# T962a-P1.net
KiCad netlist of a schematic drawn in Altium Designer
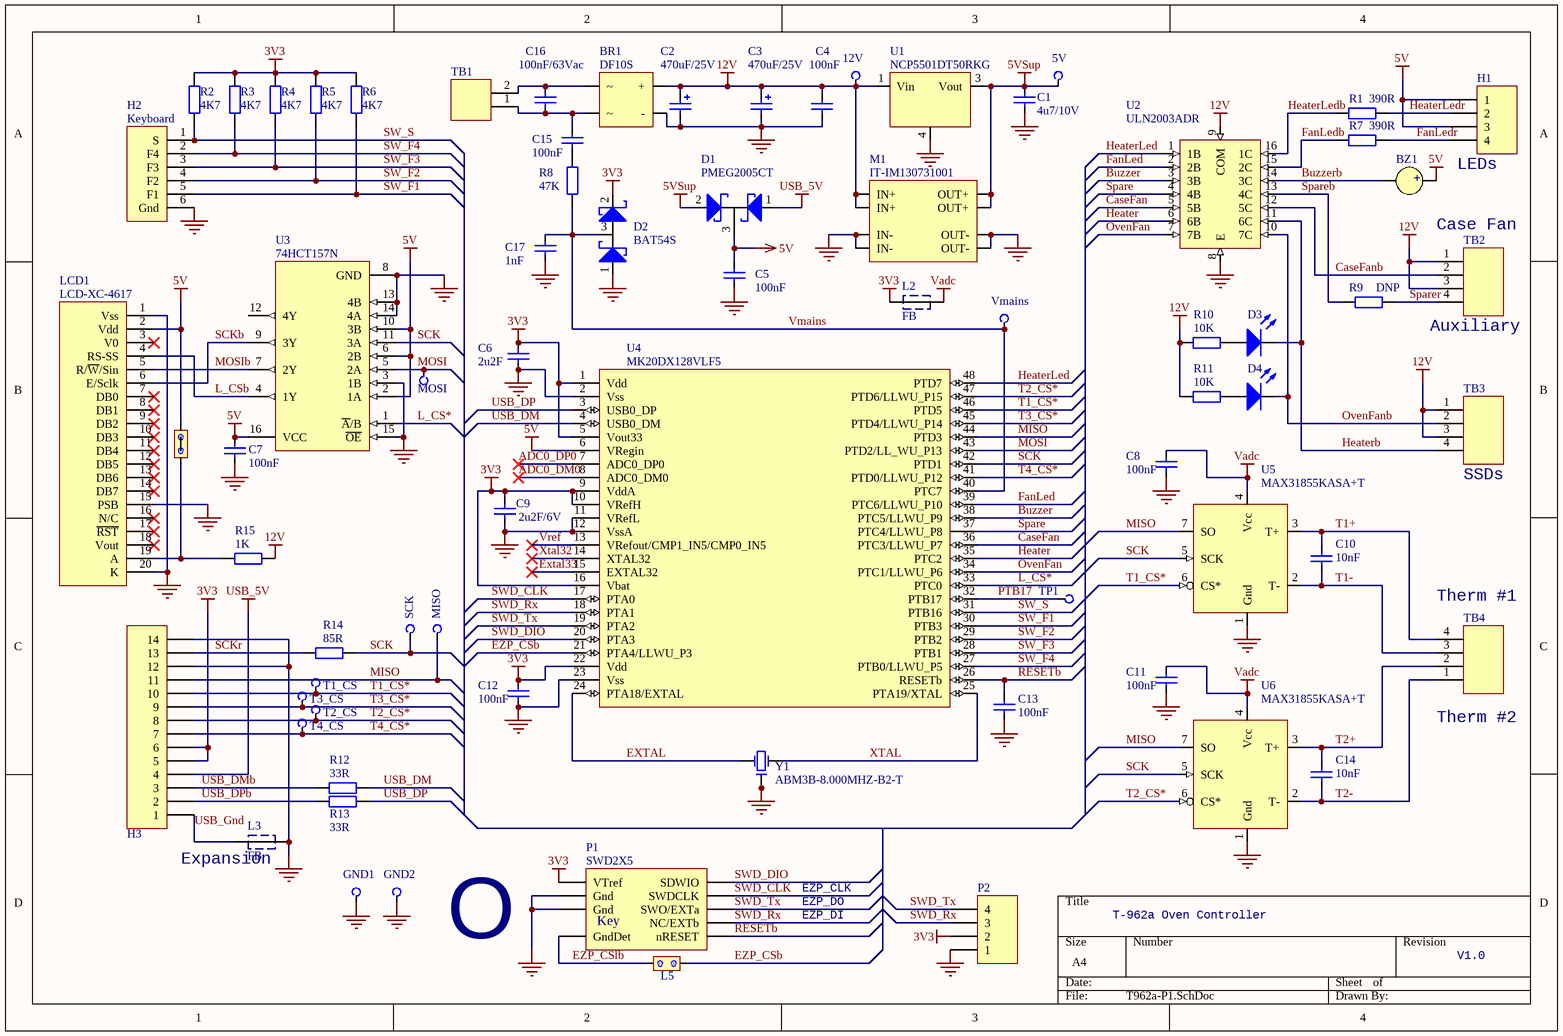
[diagram p0: T962a-P1.SchDoc]

(export (version "E")
  (design (tool "Eeschema 10.0.6"))
  (components
    (comp (ref "5V")
      (value "TP")
      (footprint "PCBPIN - 0.9mm")
      (description "Test Point")
      (libsource (lib "MyLibrary") (part "TP"))
    )
    (comp (ref "12V")
      (value "TP")
      (footprint "PCBPIN - 0.9mm")
      (description "Test Point")
      (libsource (lib "MyLibrary") (part "TP"))
    )
    (comp (ref "BR1")
      (value "DF10S")
      (footprint "Bridge-SMT")
      (description "bRIDGE rECTIFIER")
      (libsource (lib "MySchLib") (part "DF10S"))
    )
    (comp (ref "BZ1")
      (value "Buzzer_PCB")
      (footprint "BUZZER_Small")
      (description "Buzzer (Adafruit 1536)")
      (libsource (lib "MyLibrary") (part "Buzzer_PCB"))
    )
    (comp (ref "C1")
      (value "4u7/10V")
      (footprint "CCNP2012-0805")
      (description "Capacitor SMT 0805")
      (fields
        (field (name "MANUFACTURER") "Generic Components")
        (field (name "PUBLISHER") "Altium Hobart Technology Centre")
      )
      (libsource (lib "MyLibrary") (part "Cap_CCNP_0805"))
    )
    (comp (ref "C2")
      (value "470uF/25V")
      (footprint "RB5/10x13mm")
      (description "Polarized Capacitor")
      (fields
        (field (name "MANUFACTURER") "Generic Components")
        (field (name "PUBLISHER") "Altium Hobart Technology Centre")
      )
      (libsource (lib "MySchLib") (part "Cap-25ZLS470MEFC10X12"))
    )
    (comp (ref "C3")
      (value "470uF/25V")
      (footprint "RB5/10x13mm")
      (description "Polarized Capacitor")
      (fields
        (field (name "MANUFACTURER") "Generic Components")
        (field (name "PUBLISHER") "Altium Hobart Technology Centre")
      )
      (libsource (lib "MySchLib") (part "Cap-25ZLS470MEFC10X12"))
    )
    (comp (ref "C4")
      (value "100nF")
      (footprint "CCNP2012-0805")
      (description "Capacitor")
      (fields
        (field (name "MANUFACTURER") "Generic Components")
        (field (name "PUBLISHER") "Altium Hobart Technology Centre")
      )
      (libsource (lib "MyLibrary") (part "Cap"))
    )
    (comp (ref "C5")
      (value "100nF")
      (footprint "CCNP2012-0805")
      (description "Capacitor")
      (fields
        (field (name "MANUFACTURER") "Generic Components")
        (field (name "PUBLISHER") "Altium Hobart Technology Centre")
      )
      (libsource (lib "MyLibrary") (part "Cap"))
    )
    (comp (ref "C6")
      (value "2u2F")
      (footprint "CCNP2012-0805")
      (description "Capacitor")
      (fields
        (field (name "MANUFACTURER") "Generic Components")
        (field (name "PUBLISHER") "Altium Hobart Technology Centre")
      )
      (libsource (lib "MyLibrary") (part "Cap"))
    )
    (comp (ref "C7")
      (value "100nF")
      (footprint "CCNP2012-0805")
      (description "Capacitor")
      (fields
        (field (name "MANUFACTURER") "Generic Components")
        (field (name "PUBLISHER") "Altium Hobart Technology Centre")
      )
      (libsource (lib "MyLibrary") (part "Cap"))
    )
    (comp (ref "C8")
      (value "100nF")
      (footprint "CCNP2012-0805")
      (description "Capacitor SMT 0805")
      (fields
        (field (name "MANUFACTURER") "Generic Components")
        (field (name "PUBLISHER") "Altium Hobart Technology Centre")
      )
      (libsource (lib "MyLibrary") (part "Cap_CCNP_0805"))
    )
    (comp (ref "C9")
      (value "2u2F/6V")
      (footprint "CCNP2012-0805")
      (description "Capacitor")
      (fields
        (field (name "MANUFACTURER") "Generic Components")
        (field (name "PUBLISHER") "Altium Hobart Technology Centre")
      )
      (libsource (lib "MyLibrary") (part "Cap"))
    )
    (comp (ref "C10")
      (value "10nF")
      (footprint "CCNP2012-0805")
      (description "Capacitor SMT 0805")
      (fields
        (field (name "MANUFACTURER") "Generic Components")
        (field (name "PUBLISHER") "Altium Hobart Technology Centre")
      )
      (libsource (lib "MyLibrary") (part "Cap_CCNP_0805"))
    )
    (comp (ref "C11")
      (value "100nF")
      (footprint "CCNP2012-0805")
      (description "Capacitor SMT 0805")
      (fields
        (field (name "MANUFACTURER") "Generic Components")
        (field (name "PUBLISHER") "Altium Hobart Technology Centre")
      )
      (libsource (lib "MyLibrary") (part "Cap_CCNP_0805"))
    )
    (comp (ref "C12")
      (value "100nF")
      (footprint "CCNP2012-0805")
      (description "Capacitor")
      (fields
        (field (name "MANUFACTURER") "Generic Components")
        (field (name "PUBLISHER") "Altium Hobart Technology Centre")
      )
      (libsource (lib "MyLibrary") (part "Cap"))
    )
    (comp (ref "C13")
      (value "100nF")
      (footprint "CCNP2012-0805")
      (description "Capacitor SMT 0805")
      (fields
        (field (name "MANUFACTURER") "Generic Components")
        (field (name "PUBLISHER") "Altium Hobart Technology Centre")
      )
      (libsource (lib "MyLibrary") (part "Cap_CCNP_0805"))
    )
    (comp (ref "C14")
      (value "10nF")
      (footprint "CCNP2012-0805")
      (description "Capacitor SMT 0805")
      (fields
        (field (name "MANUFACTURER") "Generic Components")
        (field (name "PUBLISHER") "Altium Hobart Technology Centre")
      )
      (libsource (lib "MyLibrary") (part "Cap_CCNP_0805"))
    )
    (comp (ref "C15")
      (value "100nF")
      (footprint "CCNP2012-0805")
      (description "Capacitor")
      (fields
        (field (name "MANUFACTURER") "Generic Components")
        (field (name "PUBLISHER") "Altium Hobart Technology Centre")
      )
      (libsource (lib "MyLibrary") (part "Cap"))
    )
    (comp (ref "C16")
      (value "100nF/63Vac")
      (footprint "CAP - small MKT")
      (description "Capacitor")
      (fields
        (field (name "MANUFACTURER") "Generic Components")
        (field (name "PUBLISHER") "Altium Hobart Technology Centre")
      )
      (libsource (lib "MyLibrary") (part "Cap"))
    )
    (comp (ref "C17")
      (value "1nF")
      (footprint "CCNP2012-0805")
      (description "Capacitor")
      (fields
        (field (name "MANUFACTURER") "Generic Components")
        (field (name "PUBLISHER") "Altium Hobart Technology Centre")
      )
      (libsource (lib "MyLibrary") (part "Cap"))
    )
    (comp (ref "D1")
      (value "PMEG2005CT")
      (footprint "SOT23")
      (description "Dual Schottky Diode (SMT)")
      (libsource (lib "MyLibrary") (part "PMEG2005CT"))
    )
    (comp (ref "D2")
      (value "BAT54S")
      (footprint "SOT23")
      (description "Dual Diode (SMT)")
      (libsource (lib "MyLibrary") (part "BAT54S"))
    )
    (comp (ref "D3")
      (value "LED Red")
      (footprint "LED-SMT-2")
      (description "LED (Red SMT)")
      (fields (field (name "MANUFACTURER") "Generic Components") (field (name "PUBLISHER") "Altium Limited"))
      (libsource (lib "MyLibrary") (part "LED SMT,Red"))
    )
    (comp (ref "D4")
      (value "LED Red")
      (footprint "LED-SMT-2")
      (description "LED (Red SMT)")
      (fields (field (name "MANUFACTURER") "Generic Components") (field (name "PUBLISHER") "Altium Limited"))
      (libsource (lib "MyLibrary") (part "LED SMT,Red"))
    )
    (comp (ref "GND1")
      (value "TP")
      (footprint "PCBPIN - 0.9mm")
      (description "Test Point")
      (libsource (lib "MyLibrary") (part "TP"))
    )
    (comp (ref "GND2")
      (value "TP")
      (footprint "PCBPIN - 0.9mm")
      (description "Test Point")
      (libsource (lib "MyLibrary") (part "TP"))
    )
    (comp (ref "H1")
      (value "Header 1x4")
      (footprint "HDR1X4S")
      (description "Header, 5-Pin, Right Angle")
      (fields (field (name "PUBLISHER") "Altium Limited"))
      (libsource (lib "") (part "Header 1x4_1"))
    )
    (comp (ref "H2")
      (value "Keyboard")
      (footprint "HDR1X6H")
      (description "Header, 6-Pin")
      (fields (field (name "PUBLISHER") "Altium Limited"))
      (libsource (lib "Miscellaneous Connectors") (part "Header 6"))
    )
    (comp (ref "H3")
      (value "2x5 Header")
      (footprint "HDR2X7H")
      (description "Header 2x7")
      (libsource (lib "MyLibrary") (part "Header 2x7H"))
    )
    (comp (ref "L2")
      (value "FB")
      (footprint "CR2012-0805")
      (description "Ferrite Bead (0805) 0.045OHM, 2A")
      (libsource (lib "MyLibrary") (part "Ferrite Bead 0805"))
    )
    (comp (ref "L3")
      (value "FB")
      (footprint "CR2012-0805")
      (description "Ferrite Bead (0805) 0.045OHM, 2A")
      (libsource (lib "MyLibrary") (part "Ferrite Bead 0805"))
    )
    (comp (ref "L5")
      (value "LinkOpen")
      (footprint "SolderBridge(Open)")
      (libsource (lib "MyLibrary") (part "LinkOpen"))
    )
    (comp (ref "L6")
      (value "LinkClosed")
      (footprint "SolderBridge(Closed)")
      (libsource (lib "MyLibrary") (part "LinkClosed"))
    )
    (comp (ref "LCD1")
      (value "LCD-XC-4617")
      (footprint "LCD_XC-4617")
      (description "LCD 128 x 64 pixel, ST7920 controller & contrast pot (Jaycar XC-4617)")
      (libsource (lib "MyLibrary") (part "LCD-XC-4617"))
    )
    (comp (ref "Logo1")
      (value "OSHW Logo")
      (footprint "OSHW")
      (libsource (lib "MyLibrary") (part "OSHW Logo"))
    )
    (comp (ref "M1")
      (value "IT-IM130731001")
      (footprint "IT-IM130731001")
      (description "Itead Buck converter")
      (libsource (lib "MyLibrary") (part "IT-IM130731001"))
    )
    (comp (ref "MISO")
      (value "TP")
      (footprint "PCBPIN - 0.9mm")
      (description "Test Point")
      (libsource (lib "MyLibrary") (part "TP"))
    )
    (comp (ref "MOSI")
      (value "TP")
      (footprint "PCBPIN - 0.9mm")
      (description "Test Point")
      (libsource (lib "MyLibrary") (part "TP"))
    )
    (comp (ref "P1")
      (value "SWD2X5")
      (footprint "SWD-2x5")
      (description "SWD Connector 2x5-Pin")
      (fields (field (name "PUBLISHER") "Altium Limited"))
      (libsource (lib "MySchLib") (part "SWD2X5"))
    )
    (comp (ref "P2")
      (value "Header 1x4")
      (footprint "HDR1X4S")
      (description "Header, 5-Pin, Right Angle")
      (fields (field (name "PUBLISHER") "Altium Limited"))
      (libsource (lib "MyLibrary") (part "Header 1x4"))
    )
    (comp (ref "R1")
      (value "390R")
      (footprint "CR2012-0805")
      (description "Resistor")
      (fields
        (field (name "MANUFACTURER") "Generic Components")
        (field (name "PUBLISHER") "Altium Hobart Technology Centre")
      )
      (libsource (lib "") (part "Res_CR0805_1"))
    )
    (comp (ref "R2")
      (value "4K7")
      (footprint "CR2012-0805")
      (description "Resistor")
      (fields
        (field (name "MANUFACTURER") "Generic Components")
        (field (name "PUBLISHER") "Altium Hobart Technology Centre")
      )
      (libsource (lib "MyLibrary") (part "Res_CR0805"))
    )
    (comp (ref "R3")
      (value "4K7")
      (footprint "CR2012-0805")
      (description "Resistor")
      (fields
        (field (name "MANUFACTURER") "Generic Components")
        (field (name "PUBLISHER") "Altium Hobart Technology Centre")
      )
      (libsource (lib "MyLibrary") (part "Res_CR0805"))
    )
    (comp (ref "R4")
      (value "4K7")
      (footprint "CR2012-0805")
      (description "Resistor")
      (fields
        (field (name "MANUFACTURER") "Generic Components")
        (field (name "PUBLISHER") "Altium Hobart Technology Centre")
      )
      (libsource (lib "MyLibrary") (part "Res_CR0805"))
    )
    (comp (ref "R5")
      (value "4K7")
      (footprint "CR2012-0805")
      (description "Resistor")
      (fields
        (field (name "MANUFACTURER") "Generic Components")
        (field (name "PUBLISHER") "Altium Hobart Technology Centre")
      )
      (libsource (lib "MyLibrary") (part "Res_CR0805"))
    )
    (comp (ref "R6")
      (value "4K7")
      (footprint "CR2012-0805")
      (description "Resistor")
      (fields
        (field (name "MANUFACTURER") "Generic Components")
        (field (name "PUBLISHER") "Altium Hobart Technology Centre")
      )
      (libsource (lib "MyLibrary") (part "Res_CR0805"))
    )
    (comp (ref "R7")
      (value "390R")
      (footprint "CR2012-0805")
      (description "Resistor")
      (fields
        (field (name "MANUFACTURER") "Generic Components")
        (field (name "PUBLISHER") "Altium Hobart Technology Centre")
      )
      (libsource (lib "") (part "Res_CR0805_1"))
    )
    (comp (ref "R8")
      (value "47K")
      (footprint "CR2012-0805")
      (description "Resistor")
      (fields
        (field (name "MANUFACTURER") "Generic Components")
        (field (name "PUBLISHER") "Altium Hobart Technology Centre")
      )
      (libsource (lib "MyLibrary") (part "Res_CR0805"))
    )
    (comp (ref "R9")
      (value "DNP")
      (footprint "CR2012-0805")
      (description "Resistor")
      (fields
        (field (name "MANUFACTURER") "Generic Components")
        (field (name "PUBLISHER") "Altium Hobart Technology Centre")
      )
      (libsource (lib "") (part "Res_CR0805_1"))
    )
    (comp (ref "R10")
      (value "10K")
      (footprint "CR2012-0805")
      (description "Resistor")
      (fields
        (field (name "MANUFACTURER") "Generic Components")
        (field (name "PUBLISHER") "Altium Hobart Technology Centre")
      )
      (libsource (lib "") (part "Res_CR0805_1"))
    )
    (comp (ref "R11")
      (value "10K")
      (footprint "CR2012-0805")
      (description "Resistor")
      (fields
        (field (name "MANUFACTURER") "Generic Components")
        (field (name "PUBLISHER") "Altium Hobart Technology Centre")
      )
      (libsource (lib "") (part "Res_CR0805_1"))
    )
    (comp (ref "R12")
      (value "33R")
      (footprint "CR2012-0805")
      (description "Resistor")
      (fields
        (field (name "MANUFACTURER") "Generic Components")
        (field (name "PUBLISHER") "Altium Hobart Technology Centre")
      )
      (libsource (lib "MyLibrary") (part "Res_CR0805"))
    )
    (comp (ref "R13")
      (value "33R")
      (footprint "CR2012-0805")
      (description "Resistor")
      (fields
        (field (name "MANUFACTURER") "Generic Components")
        (field (name "PUBLISHER") "Altium Hobart Technology Centre")
      )
      (libsource (lib "MyLibrary") (part "Res_CR0805"))
    )
    (comp (ref "R14")
      (value "85R")
      (footprint "CR2012-0805")
      (description "Resistor")
      (fields
        (field (name "MANUFACTURER") "Generic Components")
        (field (name "PUBLISHER") "Altium Hobart Technology Centre")
      )
      (libsource (lib "MyLibrary") (part "Res_CR0805"))
    )
    (comp (ref "R15")
      (value "1K")
      (footprint "CR2012-0805")
      (description "Resistor")
      (fields
        (field (name "MANUFACTURER") "Generic Components")
        (field (name "PUBLISHER") "Altium Hobart Technology Centre")
      )
      (libsource (lib "MyLibrary") (part "Res_CR0805"))
    )
    (comp (ref "SCK")
      (value "TP")
      (footprint "PCBPIN - 0.9mm")
      (description "Test Point")
      (libsource (lib "MyLibrary") (part "TP"))
    )
    (comp (ref "T1_CS")
      (value "TP")
      (footprint "PCBPIN - 0.9mm")
      (description "Test Point")
      (libsource (lib "MyLibrary") (part "TP"))
    )
    (comp (ref "T2_CS")
      (value "TP")
      (footprint "PCBPIN - 0.9mm")
      (description "Test Point")
      (libsource (lib "MyLibrary") (part "TP"))
    )
    (comp (ref "T3_CS")
      (value "TP")
      (footprint "PCBPIN - 0.9mm")
      (description "Test Point")
      (libsource (lib "MyLibrary") (part "TP"))
    )
    (comp (ref "T4_CS")
      (value "TP")
      (footprint "PCBPIN - 0.9mm")
      (description "Test Point")
      (libsource (lib "MyLibrary") (part "TP"))
    )
    (comp (ref "TB1")
      (value "Terminal2")
      (footprint "MOLEX-39544-3002")
      (description "MULTICOMP  MC24366 Wire-To-Board Terminal Block")
      (libsource (lib "MyLibrary") (part "Terminal2"))
    )
    (comp (ref "TB2")
      (value "Terminal4")
      (footprint "MOLEX-39544-3004")
      (description "MULTICOMP MC24368 Wire-To-Board Terminal Block")
      (libsource (lib "MyLibrary") (part "Terminal4"))
    )
    (comp (ref "TB3")
      (value "Terminal4")
      (footprint "MOLEX-39544-3004")
      (description "MULTICOMP MC24368 Wire-To-Board Terminal Block")
      (libsource (lib "MyLibrary") (part "Terminal4"))
    )
    (comp (ref "TB4")
      (value "Terminal4")
      (footprint "MOLEX-39544-3004")
      (description "MULTICOMP MC24368 Wire-To-Board Terminal Block")
      (libsource (lib "") (part "Terminal4_1"))
    )
    (comp (ref "TP1")
      (value "TP")
      (footprint "PCBPIN - 0.9mm")
      (description "Test Point")
      (libsource (lib "MyLibrary") (part "TP"))
    )
    (comp (ref "U1")
      (value "NCP5501DT50RKG")
      (footprint "TO-252")
      (description "Fixed LDO Voltage Regulator, 2.5V-16V in, 230mV Dropout, 5V/500mA out, TO-252-3")
      (libsource (lib "MyLibrary") (part "NCP5501DT50RKG"))
    )
    (comp (ref "U2")
      (value "ULN2003ADR")
      (footprint "SO-16_N")
      (libsource (lib "MyLibrary") (part "ULN2003ADR"))
    )
    (comp (ref "U3")
      (value "74HCT157N")
      (footprint "SO-16_N")
      (description "Quad 2-1 Multiplexor")
      (libsource (lib "MyLibrary") (part "74HCT157N"))
    )
    (comp (ref "U4")
      (value "MK20DX128VLF5")
      (footprint "TSQFP50P900X900-48M")
      (description "Arm Cortex M4")
      (libsource (lib "MyLibrary") (part "MK20DX128VLF5"))
    )
    (comp (ref "U5")
      (value "MAX31855KASA+T")
      (footprint "SO-8_L")
      (libsource (lib "MySchLib") (part "MAX31855KASA+T"))
    )
    (comp (ref "U6")
      (value "MAX31855KASA+T")
      (footprint "SO-8_L")
      (libsource (lib "MySchLib") (part "MAX31855KASA+T"))
    )
    (comp (ref "Vmains")
      (value "TP")
      (footprint "PCBPIN - 0.9mm")
      (description "Test Point")
      (libsource (lib "MyLibrary") (part "TP"))
    )
    (comp (ref "Y1")
      (value "ABM3B-8.000MHZ-B2-T")
      (footprint "Crystal_SMT - ABM3B")
      (description "Crystal 8MHz (MINIATURE SMT ABM3B)")
      (fields
        (field (name "MANUFACTURER") "Generic Components")
        (field (name "PUBLISHER") "Altium Hobart Technology Centre")
      )
      (libsource (lib "MyLibrary") (part "ABM3B-8.000MHZ-B2-T"))
    )
  )
  (nets
    (net (code "1") (name "/ADC0_DM0") (class "Default")
      (node (ref "U4") (pin "8") (pinfunction "ADC0_DM0_8") (pintype "passive+no_connect"))
    )
    (net (code "2") (name "/ADC0_DP0") (class "Default")
      (node (ref "U4") (pin "7") (pinfunction "ADC0_DP0_7") (pintype "passive+no_connect"))
    )
    (net (code "3") (name "/Buzzer") (class "Default")
      (node (ref "U2") (pin "3") (pinfunction "3B_3") (pintype "input"))
      (node (ref "U4") (pin "38") (pinfunction "PTC5/LLWU_P9_38") (pintype "bidirectional"))
    )
    (net (code "4") (name "/Buzzerb") (class "Default")
      (node (ref "BZ1") (pin "1") (pinfunction "1_1") (pintype "passive"))
      (node (ref "U2") (pin "14") (pinfunction "3C_14") (pintype "input"))
    )
    (net (code "5") (name "/CaseFan") (class "Default")
      (node (ref "U2") (pin "5") (pinfunction "5B_5") (pintype "input"))
      (node (ref "U4") (pin "36") (pinfunction "PTC3/LLWU_P7_36") (pintype "bidirectional"))
    )
    (net (code "6") (name "/CaseFanb") (class "Default")
      (node (ref "TB2") (pin "2") (pinfunction "2_2") (pintype "passive"))
      (node (ref "U2") (pin "12") (pinfunction "5C_12") (pintype "input"))
    )
    (net (code "7") (name "/EXTAL") (class "Default")
      (node (ref "U4") (pin "24") (pinfunction "PTA18/EXTAL_24") (pintype "bidirectional"))
      (node (ref "Y1") (pin "1") (pinfunction "OSC1_1") (pintype "passive"))
    )
    (net (code "8") (name "/EZP_CSb") (class "Default")
      (node (ref "L5") (pin "2") (pintype "passive"))
      (node (ref "U4") (pin "21") (pinfunction "PTA4/LLWU_P3_21") (pintype "bidirectional"))
    )
    (net (code "9") (name "/EZP_CSlb") (class "Default")
      (node (ref "L5") (pin "1") (pintype "passive"))
      (node (ref "P1") (pin "9") (pinfunction "GndDet_9") (pintype "passive"))
    )
    (net (code "10") (name "/Extal33") (class "Default")
      (node (ref "U4") (pin "15") (pinfunction "EXTAL32_15") (pintype "passive+no_connect"))
    )
    (net (code "11") (name "/FanLed") (class "Default")
      (node (ref "U2") (pin "2") (pinfunction "2B_2") (pintype "input"))
      (node (ref "U4") (pin "39") (pinfunction "PTC6/LLWU_P10_39") (pintype "bidirectional"))
    )
    (net (code "12") (name "/FanLedb") (class "Default")
      (node (ref "R7") (pin "1") (pinfunction "1_1") (pintype "passive"))
      (node (ref "U2") (pin "15") (pinfunction "2C_15") (pintype "input"))
    )
    (net (code "13") (name "/FanLedr") (class "Default")
      (node (ref "H1") (pin "4") (pinfunction "4_4") (pintype "passive"))
      (node (ref "R7") (pin "2") (pinfunction "2_2") (pintype "passive"))
    )
    (net (code "14") (name "/Heater") (class "Default")
      (node (ref "U2") (pin "6") (pinfunction "6B_6") (pintype "input"))
      (node (ref "U4") (pin "35") (pinfunction "PTC2_35") (pintype "bidirectional"))
    )
    (net (code "15") (name "/HeaterLed") (class "Default")
      (node (ref "U2") (pin "1") (pinfunction "1B_1") (pintype "input"))
      (node (ref "U4") (pin "48") (pinfunction "PTD7_48") (pintype "bidirectional"))
    )
    (net (code "16") (name "/HeaterLedb") (class "Default")
      (node (ref "R1") (pin "1") (pinfunction "1_1") (pintype "passive"))
      (node (ref "U2") (pin "16") (pinfunction "1C_16") (pintype "input"))
    )
    (net (code "17") (name "/HeaterLedr") (class "Default")
      (node (ref "H1") (pin "2") (pinfunction "2_2") (pintype "passive"))
      (node (ref "R1") (pin "2") (pinfunction "2_2") (pintype "passive"))
    )
    (net (code "18") (name "/Heaterb") (class "Default")
      (node (ref "D3") (pin "K") (pinfunction "K_K") (pintype "passive"))
      (node (ref "TB3") (pin "4") (pinfunction "4_4") (pintype "passive"))
      (node (ref "U2") (pin "11") (pinfunction "6C_11") (pintype "input"))
    )
    (net (code "19") (name "/L_CS*") (class "Default")
      (node (ref "U3") (pin "1") (pinfunction "~{A}/B_1") (pintype "input"))
      (node (ref "U4") (pin "33") (pinfunction "PTC0_33") (pintype "bidirectional"))
    )
    (net (code "20") (name "/L_CSb") (class "Default")
      (node (ref "LCD1") (pin "4") (pinfunction "RS-SS_4") (pintype "passive"))
      (node (ref "U3") (pin "4") (pinfunction "1Y_4") (pintype "output"))
    )
    (net (code "21") (name "/MISO") (class "Default")
      (node (ref "H3") (pin "11") (pinfunction "11_11") (pintype "passive"))
      (node (ref "MISO") (pin "1") (pinfunction "TP_1") (pintype "passive"))
      (node (ref "U4") (pin "44") (pinfunction "PTD3_44") (pintype "bidirectional"))
      (node (ref "U5") (pin "7") (pinfunction "SO_7") (pintype "tri_state"))
      (node (ref "U6") (pin "7") (pinfunction "SO_7") (pintype "tri_state"))
    )
    (net (code "22") (name "/MOSI") (class "Default")
      (node (ref "MOSI") (pin "1") (pinfunction "TP_1") (pintype "passive"))
      (node (ref "U3") (pin "5") (pinfunction "2A_5") (pintype "input"))
      (node (ref "U4") (pin "43") (pinfunction "PTD2/LL_WU_P13_43") (pintype "bidirectional"))
    )
    (net (code "23") (name "/MOSIb") (class "Default")
      (node (ref "LCD1") (pin "5") (pinfunction "R/~{W}/Sin_5") (pintype "passive"))
      (node (ref "U3") (pin "7") (pinfunction "2Y_7") (pintype "output"))
    )
    (net (code "24") (name "/OvenFan") (class "Default")
      (node (ref "U2") (pin "7") (pinfunction "7B_7") (pintype "input"))
      (node (ref "U4") (pin "34") (pinfunction "PTC1/LLWU_P6_34") (pintype "bidirectional"))
    )
    (net (code "25") (name "/OvenFanb") (class "Default")
      (node (ref "D4") (pin "K") (pinfunction "K_K") (pintype "passive"))
      (node (ref "TB3") (pin "2") (pinfunction "2_2") (pintype "passive"))
      (node (ref "U2") (pin "10") (pinfunction "7C_10") (pintype "input"))
    )
    (net (code "26") (name "/PTB17") (class "Default")
      (node (ref "TP1") (pin "1") (pinfunction "TP_1") (pintype "passive"))
      (node (ref "U4") (pin "32") (pinfunction "PTB17_32") (pintype "bidirectional"))
    )
    (net (code "27") (name "/RESETb") (class "Default")
      (node (ref "C13") (pin "2") (pinfunction "2_2") (pintype "passive"))
      (node (ref "P1") (pin "10") (pinfunction "nRESET_10") (pintype "passive"))
      (node (ref "U4") (pin "26") (pinfunction "RESETb_26") (pintype "bidirectional"))
    )
    (net (code "28") (name "/SCK") (class "Default")
      (node (ref "R14") (pin "2") (pinfunction "2_2") (pintype "passive"))
      (node (ref "SCK") (pin "1") (pinfunction "TP_1") (pintype "passive"))
      (node (ref "U3") (pin "11") (pinfunction "3A_11") (pintype "input"))
      (node (ref "U4") (pin "42") (pinfunction "PTD1_42") (pintype "bidirectional"))
      (node (ref "U5") (pin "5") (pinfunction "SCK_5") (pintype "input"))
      (node (ref "U6") (pin "5") (pinfunction "SCK_5") (pintype "input"))
    )
    (net (code "29") (name "/SCKb") (class "Default")
      (node (ref "LCD1") (pin "6") (pinfunction "E/Sclk_6") (pintype "passive"))
      (node (ref "U3") (pin "9") (pinfunction "3Y_9") (pintype "output"))
    )
    (net (code "30") (name "/SCKr") (class "Default")
      (node (ref "H3") (pin "13") (pinfunction "13_13") (pintype "passive"))
      (node (ref "R14") (pin "1") (pinfunction "1_1") (pintype "passive"))
    )
    (net (code "31") (name "/SWD_CLK") (class "Default")
      (node (ref "P1") (pin "4") (pinfunction "SWDCLK_4") (pintype "passive"))
      (node (ref "U4") (pin "17") (pinfunction "PTA0_17") (pintype "bidirectional"))
    )
    (net (code "32") (name "/SWD_DIO") (class "Default")
      (node (ref "P1") (pin "2") (pinfunction "SDWIO_2") (pintype "passive"))
      (node (ref "U4") (pin "20") (pinfunction "PTA3_20") (pintype "bidirectional"))
    )
    (net (code "33") (name "/SWD_Rx") (class "Default")
      (node (ref "P1") (pin "8") (pinfunction "NC/EXTb_8") (pintype "passive"))
      (node (ref "P2") (pin "3") (pinfunction "3_3") (pintype "passive"))
      (node (ref "U4") (pin "18") (pinfunction "PTA1_18") (pintype "bidirectional"))
    )
    (net (code "34") (name "/SWD_Tx") (class "Default")
      (node (ref "P1") (pin "6") (pinfunction "SWO/EXTa_6") (pintype "passive"))
      (node (ref "P2") (pin "4") (pinfunction "4_4") (pintype "passive"))
      (node (ref "U4") (pin "19") (pinfunction "PTA2_19") (pintype "bidirectional"))
    )
    (net (code "35") (name "/SW_F1") (class "Default")
      (node (ref "H2") (pin "5") (pinfunction "F1_5") (pintype "passive"))
      (node (ref "R6") (pin "1") (pinfunction "1_1") (pintype "passive"))
      (node (ref "U4") (pin "30") (pinfunction "PTB3_30") (pintype "bidirectional"))
    )
    (net (code "36") (name "/SW_F2") (class "Default")
      (node (ref "H2") (pin "4") (pinfunction "F2_4") (pintype "passive"))
      (node (ref "R5") (pin "1") (pinfunction "1_1") (pintype "passive"))
      (node (ref "U4") (pin "29") (pinfunction "PTB2_29") (pintype "bidirectional"))
    )
    (net (code "37") (name "/SW_F3") (class "Default")
      (node (ref "H2") (pin "3") (pinfunction "F3_3") (pintype "passive"))
      (node (ref "R4") (pin "1") (pinfunction "1_1") (pintype "passive"))
      (node (ref "U4") (pin "28") (pinfunction "PTB1_28") (pintype "bidirectional"))
    )
    (net (code "38") (name "/SW_F4") (class "Default")
      (node (ref "H2") (pin "2") (pinfunction "F4_2") (pintype "passive"))
      (node (ref "R3") (pin "1") (pinfunction "1_1") (pintype "passive"))
      (node (ref "U4") (pin "27") (pinfunction "PTB0/LLWU_P5_27") (pintype "bidirectional"))
    )
    (net (code "39") (name "/SW_S") (class "Default")
      (node (ref "H2") (pin "1") (pinfunction "S_1") (pintype "passive"))
      (node (ref "R2") (pin "1") (pinfunction "1_1") (pintype "passive"))
      (node (ref "U4") (pin "31") (pinfunction "PTB16_31") (pintype "bidirectional"))
    )
    (net (code "40") (name "/Spare") (class "Default")
      (node (ref "U2") (pin "4") (pinfunction "4B_4") (pintype "input"))
      (node (ref "U4") (pin "37") (pinfunction "PTC4/LLWU_P8_37") (pintype "power_in"))
    )
    (net (code "41") (name "/Spareb") (class "Default")
      (node (ref "R9") (pin "1") (pinfunction "1_1") (pintype "passive"))
      (node (ref "U2") (pin "13") (pinfunction "4C_13") (pintype "input"))
    )
    (net (code "42") (name "/Sparer") (class "Default")
      (node (ref "R9") (pin "2") (pinfunction "2_2") (pintype "passive"))
      (node (ref "TB2") (pin "4") (pinfunction "4_4") (pintype "passive"))
    )
    (net (code "43") (name "/T1+") (class "Default")
      (node (ref "C10") (pin "2") (pinfunction "2_2") (pintype "passive"))
      (node (ref "TB4") (pin "4") (pinfunction "4_4") (pintype "passive"))
      (node (ref "U5") (pin "3") (pinfunction "T+_3") (pintype "passive"))
    )
    (net (code "44") (name "/T1-") (class "Default")
      (node (ref "C10") (pin "1") (pinfunction "1_1") (pintype "passive"))
      (node (ref "TB4") (pin "3") (pinfunction "3_3") (pintype "passive"))
      (node (ref "U5") (pin "2") (pinfunction "T-_2") (pintype "passive"))
    )
    (net (code "45") (name "/T1_CS*") (class "Default")
      (node (ref "H3") (pin "10") (pinfunction "10_10") (pintype "passive"))
      (node (ref "T1_CS") (pin "1") (pinfunction "TP_1") (pintype "passive"))
      (node (ref "U4") (pin "46") (pinfunction "PTD5_46") (pintype "bidirectional"))
      (node (ref "U5") (pin "6") (pinfunction "CS*_6") (pintype "input"))
    )
    (net (code "46") (name "/T2+") (class "Default")
      (node (ref "C14") (pin "2") (pinfunction "2_2") (pintype "passive"))
      (node (ref "TB4") (pin "2") (pinfunction "2_2") (pintype "passive"))
      (node (ref "U6") (pin "3") (pinfunction "T+_3") (pintype "passive"))
    )
    (net (code "47") (name "/T2-") (class "Default")
      (node (ref "C14") (pin "1") (pinfunction "1_1") (pintype "passive"))
      (node (ref "TB4") (pin "1") (pinfunction "1_1") (pintype "passive"))
      (node (ref "U6") (pin "2") (pinfunction "T-_2") (pintype "passive"))
    )
    (net (code "48") (name "/T2_CS*") (class "Default")
      (node (ref "H3") (pin "8") (pinfunction "8_8") (pintype "passive"))
      (node (ref "T2_CS") (pin "1") (pinfunction "TP_1") (pintype "passive"))
      (node (ref "U4") (pin "47") (pinfunction "PTD6/LLWU_P15_47") (pintype "bidirectional"))
      (node (ref "U6") (pin "6") (pinfunction "CS*_6") (pintype "input"))
    )
    (net (code "49") (name "/T3_CS*") (class "Default")
      (node (ref "H3") (pin "9") (pinfunction "9_9") (pintype "passive"))
      (node (ref "T3_CS") (pin "1") (pinfunction "TP_1") (pintype "passive"))
      (node (ref "U4") (pin "45") (pinfunction "PTD4/LLWU_P14_45") (pintype "bidirectional"))
    )
    (net (code "50") (name "/T4_CS*") (class "Default")
      (node (ref "H3") (pin "7") (pinfunction "7_7") (pintype "passive"))
      (node (ref "T4_CS") (pin "1") (pinfunction "TP_1") (pintype "passive"))
      (node (ref "U4") (pin "41") (pinfunction "PTD0/LLWU_P12_41") (pintype "bidirectional"))
    )
    (net (code "51") (name "/USB_DM") (class "Default")
      (node (ref "R12") (pin "2") (pinfunction "2_2") (pintype "passive"))
      (node (ref "U4") (pin "4") (pinfunction "USB0_DM_4") (pintype "bidirectional"))
    )
    (net (code "52") (name "/USB_DMb") (class "Default")
      (node (ref "H3") (pin "3") (pinfunction "3_3") (pintype "passive"))
      (node (ref "R12") (pin "1") (pinfunction "1_1") (pintype "passive"))
    )
    (net (code "53") (name "/USB_DP") (class "Default")
      (node (ref "R13") (pin "2") (pinfunction "2_2") (pintype "passive"))
      (node (ref "U4") (pin "3") (pinfunction "USB0_DP_3") (pintype "bidirectional"))
    )
    (net (code "54") (name "/USB_DPb") (class "Default")
      (node (ref "H3") (pin "2") (pinfunction "2_2") (pintype "passive"))
      (node (ref "R13") (pin "1") (pinfunction "1_1") (pintype "passive"))
    )
    (net (code "55") (name "/USB_Gnd") (class "Default")
      (node (ref "H3") (pin "1") (pinfunction "1_1") (pintype "passive"))
      (node (ref "L3") (pin "2") (pinfunction "2_2") (pintype "passive"))
    )
    (net (code "56") (name "/Vmains") (class "Default")
      (node (ref "C17") (pin "2") (pinfunction "2_2") (pintype "passive"))
      (node (ref "D2") (pin "3") (pinfunction "K_3") (pintype "passive"))
      (node (ref "R8") (pin "1") (pinfunction "1_1") (pintype "passive"))
      (node (ref "U4") (pin "40") (pinfunction "PTC7_40") (pintype "bidirectional"))
      (node (ref "Vmains") (pin "1") (pinfunction "TP_1") (pintype "passive"))
    )
    (net (code "57") (name "/Vref") (class "Default")
      (node (ref "U4") (pin "13") (pinfunction "VRefout/CMP1_IN5/CMP0_IN5_13") (pintype "passive+no_connect"))
    )
    (net (code "58") (name "/XTAL") (class "Default")
      (node (ref "U4") (pin "25") (pinfunction "PTA19/XTAL_25") (pintype "bidirectional"))
      (node (ref "Y1") (pin "3") (pinfunction "OSC2_3") (pintype "passive"))
    )
    (net (code "59") (name "/Xtal32") (class "Default")
      (node (ref "U4") (pin "14") (pinfunction "XTAL32_14") (pintype "passive+no_connect"))
    )
    (net (code "60") (name "3V3") (class "Default")
      (node (ref "C12") (pin "2") (pinfunction "2_2") (pintype "passive"))
      (node (ref "C6") (pin "2") (pinfunction "2_2") (pintype "passive"))
      (node (ref "C9") (pin "2") (pinfunction "2_2") (pintype "passive"))
      (node (ref "D2") (pin "2") (pinfunction "A2_2") (pintype "passive"))
      (node (ref "H3") (pin "5") (pinfunction "5_5") (pintype "passive"))
      (node (ref "H3") (pin "6") (pinfunction "6_6") (pintype "passive"))
      (node (ref "L2") (pin "1") (pinfunction "1_1") (pintype "passive"))
      (node (ref "P1") (pin "1") (pinfunction "VTref_1") (pintype "passive"))
      (node (ref "P2") (pin "2") (pinfunction "2_2") (pintype "passive"))
      (node (ref "R2") (pin "2") (pinfunction "2_2") (pintype "passive"))
      (node (ref "R3") (pin "2") (pinfunction "2_2") (pintype "passive"))
      (node (ref "R4") (pin "2") (pinfunction "2_2") (pintype "passive"))
      (node (ref "R5") (pin "2") (pinfunction "2_2") (pintype "passive"))
      (node (ref "R6") (pin "2") (pinfunction "2_2") (pintype "passive"))
      (node (ref "U4") (pin "1") (pinfunction "Vdd_1") (pintype "power_in"))
      (node (ref "U4") (pin "10") (pinfunction "VRefH_10") (pintype "passive"))
      (node (ref "U4") (pin "16") (pinfunction "Vbat_16") (pintype "passive"))
      (node (ref "U4") (pin "22") (pinfunction "Vdd_22") (pintype "power_in"))
      (node (ref "U4") (pin "5") (pinfunction "Vout33_5") (pintype "power_in"))
      (node (ref "U4") (pin "9") (pinfunction "VddA_9") (pintype "power_in"))
    )
    (net (code "61") (name "5V") (class "Default")
      (node (ref "BZ1") (pin "2") (pinfunction "+_2") (pintype "passive"))
      (node (ref "C5") (pin "2") (pinfunction "2_2") (pintype "passive"))
      (node (ref "C7") (pin "2") (pinfunction "2_2") (pintype "passive"))
      (node (ref "D1") (pin "3") (pinfunction "K_3") (pintype "passive"))
      (node (ref "H1") (pin "1") (pinfunction "1_1") (pintype "passive"))
      (node (ref "H1") (pin "3") (pinfunction "3_3") (pintype "passive"))
      (node (ref "L6") (pin "2") (pintype "passive"))
      (node (ref "LCD1") (pin "2") (pinfunction "Vdd_2") (pintype "passive"))
      (node (ref "U3") (pin "10") (pinfunction "3B_10") (pintype "input"))
      (node (ref "U3") (pin "16") (pinfunction "VCC_16") (pintype "power_in"))
      (node (ref "U3") (pin "2") (pinfunction "1A_2") (pintype "input"))
      (node (ref "U3") (pin "6") (pinfunction "2B_6") (pintype "input"))
      (node (ref "U4") (pin "6") (pinfunction "VRegin_6") (pintype "passive"))
    )
    (net (code "62") (name "5VSup") (class "Default")
      (node (ref "5V") (pin "1") (pinfunction "TP_1") (pintype "passive"))
      (node (ref "C1") (pin "2") (pinfunction "2_2") (pintype "passive"))
      (node (ref "D1") (pin "2") (pinfunction "A2_2") (pintype "passive"))
      (node (ref "M1") (pin "OUT0+") (pinfunction "OUT+_OUT0+") (pintype "power_in"))
      (node (ref "M1") (pin "OUT1+") (pinfunction "OUT+_OUT1+") (pintype "power_in"))
      (node (ref "U1") (pin "3") (pinfunction "Vout_3") (pintype "passive"))
    )
    (net (code "63") (name "12V") (class "Default")
      (node (ref "12V") (pin "1") (pinfunction "TP_1") (pintype "passive"))
      (node (ref "BR1") (pin "1") (pinfunction "+_1") (pintype "power_in"))
      (node (ref "C2") (pin "1") (pinfunction "1_1") (pintype "passive"))
      (node (ref "C3") (pin "1") (pinfunction "1_1") (pintype "passive"))
      (node (ref "C4") (pin "2") (pinfunction "2_2") (pintype "passive"))
      (node (ref "M1") (pin "IN0+") (pinfunction "IN+_IN0+") (pintype "power_in"))
      (node (ref "M1") (pin "IN1+") (pinfunction "IN+_IN1+") (pintype "power_in"))
      (node (ref "R10") (pin "1") (pinfunction "1_1") (pintype "passive"))
      (node (ref "R11") (pin "1") (pinfunction "1_1") (pintype "passive"))
      (node (ref "R15") (pin "2") (pinfunction "2_2") (pintype "passive"))
      (node (ref "TB2") (pin "1") (pinfunction "1_1") (pintype "passive"))
      (node (ref "TB2") (pin "3") (pinfunction "3_3") (pintype "passive"))
      (node (ref "TB3") (pin "1") (pinfunction "1_1") (pintype "passive"))
      (node (ref "TB3") (pin "3") (pinfunction "3_3") (pintype "passive"))
      (node (ref "U1") (pin "1") (pinfunction "Vin_1") (pintype "passive"))
      (node (ref "U2") (pin "9") (pinfunction "COM_9") (pintype "input"))
    )
    (net (code "64") (name "GND") (class "Default")
      (node (ref "BR1") (pin "2") (pinfunction "-_2") (pintype "power_in"))
      (node (ref "C1") (pin "1") (pinfunction "1_1") (pintype "passive"))
      (node (ref "C11") (pin "1") (pinfunction "1_1") (pintype "passive"))
      (node (ref "C12") (pin "1") (pinfunction "1_1") (pintype "passive"))
      (node (ref "C13") (pin "1") (pinfunction "1_1") (pintype "passive"))
      (node (ref "C17") (pin "1") (pinfunction "1_1") (pintype "passive"))
      (node (ref "C2") (pin "2") (pinfunction "2_2") (pintype "passive"))
      (node (ref "C3") (pin "2") (pinfunction "2_2") (pintype "passive"))
      (node (ref "C4") (pin "1") (pinfunction "1_1") (pintype "passive"))
      (node (ref "C5") (pin "1") (pinfunction "1_1") (pintype "passive"))
      (node (ref "C6") (pin "1") (pinfunction "1_1") (pintype "passive"))
      (node (ref "C7") (pin "1") (pinfunction "1_1") (pintype "passive"))
      (node (ref "C8") (pin "1") (pinfunction "1_1") (pintype "passive"))
      (node (ref "C9") (pin "1") (pinfunction "1_1") (pintype "passive"))
      (node (ref "D2") (pin "1") (pinfunction "A1_1") (pintype "passive"))
      (node (ref "GND1") (pin "1") (pinfunction "TP_1") (pintype "passive"))
      (node (ref "GND2") (pin "1") (pinfunction "TP_1") (pintype "passive"))
      (node (ref "H2") (pin "6") (pinfunction "Gnd_6") (pintype "passive"))
      (node (ref "H3") (pin "12") (pinfunction "12_12") (pintype "passive"))
      (node (ref "H3") (pin "14") (pinfunction "14_14") (pintype "passive"))
      (node (ref "L3") (pin "1") (pinfunction "1_1") (pintype "passive"))
      (node (ref "LCD1") (pin "1") (pinfunction "Vss_1") (pintype "passive"))
      (node (ref "LCD1") (pin "15") (pinfunction "PSB_15") (pintype "passive"))
      (node (ref "LCD1") (pin "20") (pinfunction "K_20") (pintype "passive"))
      (node (ref "M1") (pin "IN0-") (pinfunction "IN-_IN0-") (pintype "power_in"))
      (node (ref "M1") (pin "IN1-") (pinfunction "IN-_IN1-") (pintype "power_in"))
      (node (ref "M1") (pin "OUT0-") (pinfunction "OUT-_OUT0-") (pintype "power_in"))
      (node (ref "M1") (pin "OUT1-") (pinfunction "OUT-_OUT1-") (pintype "power_in"))
      (node (ref "P1") (pin "3") (pinfunction "Gnd_3") (pintype "passive"))
      (node (ref "P1") (pin "5") (pinfunction "Gnd_5") (pintype "passive"))
      (node (ref "P2") (pin "1") (pinfunction "1_1") (pintype "passive"))
      (node (ref "U1") (pin "4") (pinfunction "Gnd_(Tab)_4") (pintype "power_in"))
      (node (ref "U2") (pin "8") (pinfunction "E_8") (pintype "input"))
      (node (ref "U3") (pin "13") (pinfunction "4B_13") (pintype "input"))
      (node (ref "U3") (pin "14") (pinfunction "4A_14") (pintype "input"))
      (node (ref "U3") (pin "15") (pinfunction "~{OE}_15") (pintype "input"))
      (node (ref "U3") (pin "3") (pinfunction "1B_3") (pintype "input"))
      (node (ref "U3") (pin "8") (pinfunction "GND_8") (pintype "power_in"))
      (node (ref "U4") (pin "11") (pinfunction "VRefL_11") (pintype "passive"))
      (node (ref "U4") (pin "12") (pinfunction "VssA_12") (pintype "power_in"))
      (node (ref "U4") (pin "2") (pinfunction "Vss_2") (pintype "power_in"))
      (node (ref "U4") (pin "23") (pinfunction "Vss_23") (pintype "power_in"))
      (node (ref "U5") (pin "1") (pinfunction "Gnd_1") (pintype "power_in"))
      (node (ref "U6") (pin "1") (pinfunction "Gnd_1") (pintype "power_in"))
      (node (ref "Y1") (pin "2") (pinfunction "Gnd_2") (pintype "passive"))
      (node (ref "Y1") (pin "4") (pinfunction "Gnd_4") (pintype "passive"))
    )
    (net (code "65") (name "Net-(BR1-~-Pad3)") (class "Default")
      (node (ref "BR1") (pin "3") (pinfunction "~_3") (pintype "power_in"))
      (node (ref "C15") (pin "2") (pinfunction "2_2") (pintype "passive"))
      (node (ref "C16") (pin "1") (pinfunction "1_1") (pintype "passive"))
      (node (ref "TB1") (pin "1") (pinfunction "1_1") (pintype "passive"))
    )
    (net (code "66") (name "Net-(BR1-~-Pad4)") (class "Default")
      (node (ref "BR1") (pin "4") (pinfunction "~_4") (pintype "power_in"))
      (node (ref "C16") (pin "2") (pinfunction "2_2") (pintype "passive"))
      (node (ref "TB1") (pin "2") (pinfunction "2_2") (pintype "passive"))
    )
    (net (code "67") (name "Net-(C15-Pad1)") (class "Default")
      (node (ref "C15") (pin "1") (pinfunction "1_1") (pintype "passive"))
      (node (ref "R8") (pin "2") (pinfunction "2_2") (pintype "passive"))
    )
    (net (code "68") (name "Net-(D3-PadA)") (class "Default")
      (node (ref "D3") (pin "A") (pinfunction "A_A") (pintype "passive"))
      (node (ref "R10") (pin "2") (pinfunction "2_2") (pintype "passive"))
    )
    (net (code "69") (name "Net-(D4-PadA)") (class "Default")
      (node (ref "D4") (pin "A") (pinfunction "A_A") (pintype "passive"))
      (node (ref "R11") (pin "2") (pinfunction "2_2") (pintype "passive"))
    )
    (net (code "70") (name "Net-(LCD1-A)") (class "Default")
      (node (ref "L6") (pin "1") (pintype "passive"))
      (node (ref "LCD1") (pin "19") (pinfunction "A_19") (pintype "passive"))
      (node (ref "R15") (pin "1") (pinfunction "1_1") (pintype "passive"))
    )
    (net (code "71") (name "USB_5V") (class "Default")
      (node (ref "D1") (pin "1") (pinfunction "A1_1") (pintype "passive"))
      (node (ref "H3") (pin "4") (pinfunction "4_4") (pintype "passive"))
    )
    (net (code "72") (name "Vadc") (class "Default")
      (node (ref "C11") (pin "2") (pinfunction "2_2") (pintype "passive"))
      (node (ref "C8") (pin "2") (pinfunction "2_2") (pintype "passive"))
      (node (ref "L2") (pin "2") (pinfunction "2_2") (pintype "passive"))
      (node (ref "U5") (pin "4") (pinfunction "Vcc_4") (pintype "power_in"))
      (node (ref "U6") (pin "4") (pinfunction "Vcc_4") (pintype "power_in"))
    )
    (net (code "73") (name "unconnected-(LCD1-DB0-Pad7)") (class "Default")
      (node (ref "LCD1") (pin "7") (pinfunction "DB0_7") (pintype "passive+no_connect"))
    )
    (net (code "74") (name "unconnected-(LCD1-DB1-Pad8)") (class "Default")
      (node (ref "LCD1") (pin "8") (pinfunction "DB1_8") (pintype "passive+no_connect"))
    )
    (net (code "75") (name "unconnected-(LCD1-DB2-Pad9)") (class "Default")
      (node (ref "LCD1") (pin "9") (pinfunction "DB2_9") (pintype "passive+no_connect"))
    )
    (net (code "76") (name "unconnected-(LCD1-DB3-Pad10)") (class "Default")
      (node (ref "LCD1") (pin "10") (pinfunction "DB3_10") (pintype "passive+no_connect"))
    )
    (net (code "77") (name "unconnected-(LCD1-DB4-Pad11)") (class "Default")
      (node (ref "LCD1") (pin "11") (pinfunction "DB4_11") (pintype "passive+no_connect"))
    )
    (net (code "78") (name "unconnected-(LCD1-DB5-Pad12)") (class "Default")
      (node (ref "LCD1") (pin "12") (pinfunction "DB5_12") (pintype "passive+no_connect"))
    )
    (net (code "79") (name "unconnected-(LCD1-DB6-Pad13)") (class "Default")
      (node (ref "LCD1") (pin "13") (pinfunction "DB6_13") (pintype "passive+no_connect"))
    )
    (net (code "80") (name "unconnected-(LCD1-DB7-Pad14)") (class "Default")
      (node (ref "LCD1") (pin "14") (pinfunction "DB7_14") (pintype "passive+no_connect"))
    )
    (net (code "81") (name "unconnected-(LCD1-N{slash}C-Pad16)") (class "Default")
      (node (ref "LCD1") (pin "16") (pinfunction "N/C_16") (pintype "passive+no_connect"))
    )
    (net (code "82") (name "unconnected-(LCD1-V0-Pad3)") (class "Default")
      (node (ref "LCD1") (pin "3") (pinfunction "V0_3") (pintype "passive+no_connect"))
    )
    (net (code "83") (name "unconnected-(LCD1-Vout-Pad18)") (class "Default")
      (node (ref "LCD1") (pin "18") (pinfunction "Vout_18") (pintype "passive+no_connect"))
    )
    (net (code "84") (name "unconnected-(LCD1-~{RST}-Pad17)") (class "Default")
      (node (ref "LCD1") (pin "17") (pinfunction "~{RST}_17") (pintype "passive+no_connect"))
    )
    (net (code "85") (name "unconnected-(U3-4Y-Pad12)") (class "Default")
      (node (ref "U3") (pin "12") (pinfunction "4Y_12") (pintype "output"))
    )
    (net (code "86") (name "unconnected-(U5-NC-Pad8)") (class "Default")
      (node (ref "U5") (pin "8") (pinfunction "NC_8") (pintype "passive"))
    )
    (net (code "87") (name "unconnected-(U6-NC-Pad8)") (class "Default")
      (node (ref "U6") (pin "8") (pinfunction "NC_8") (pintype "passive"))
    )
  )
)
